# DRV8711.net
KiCad netlist of a schematic drawn in EAGLE
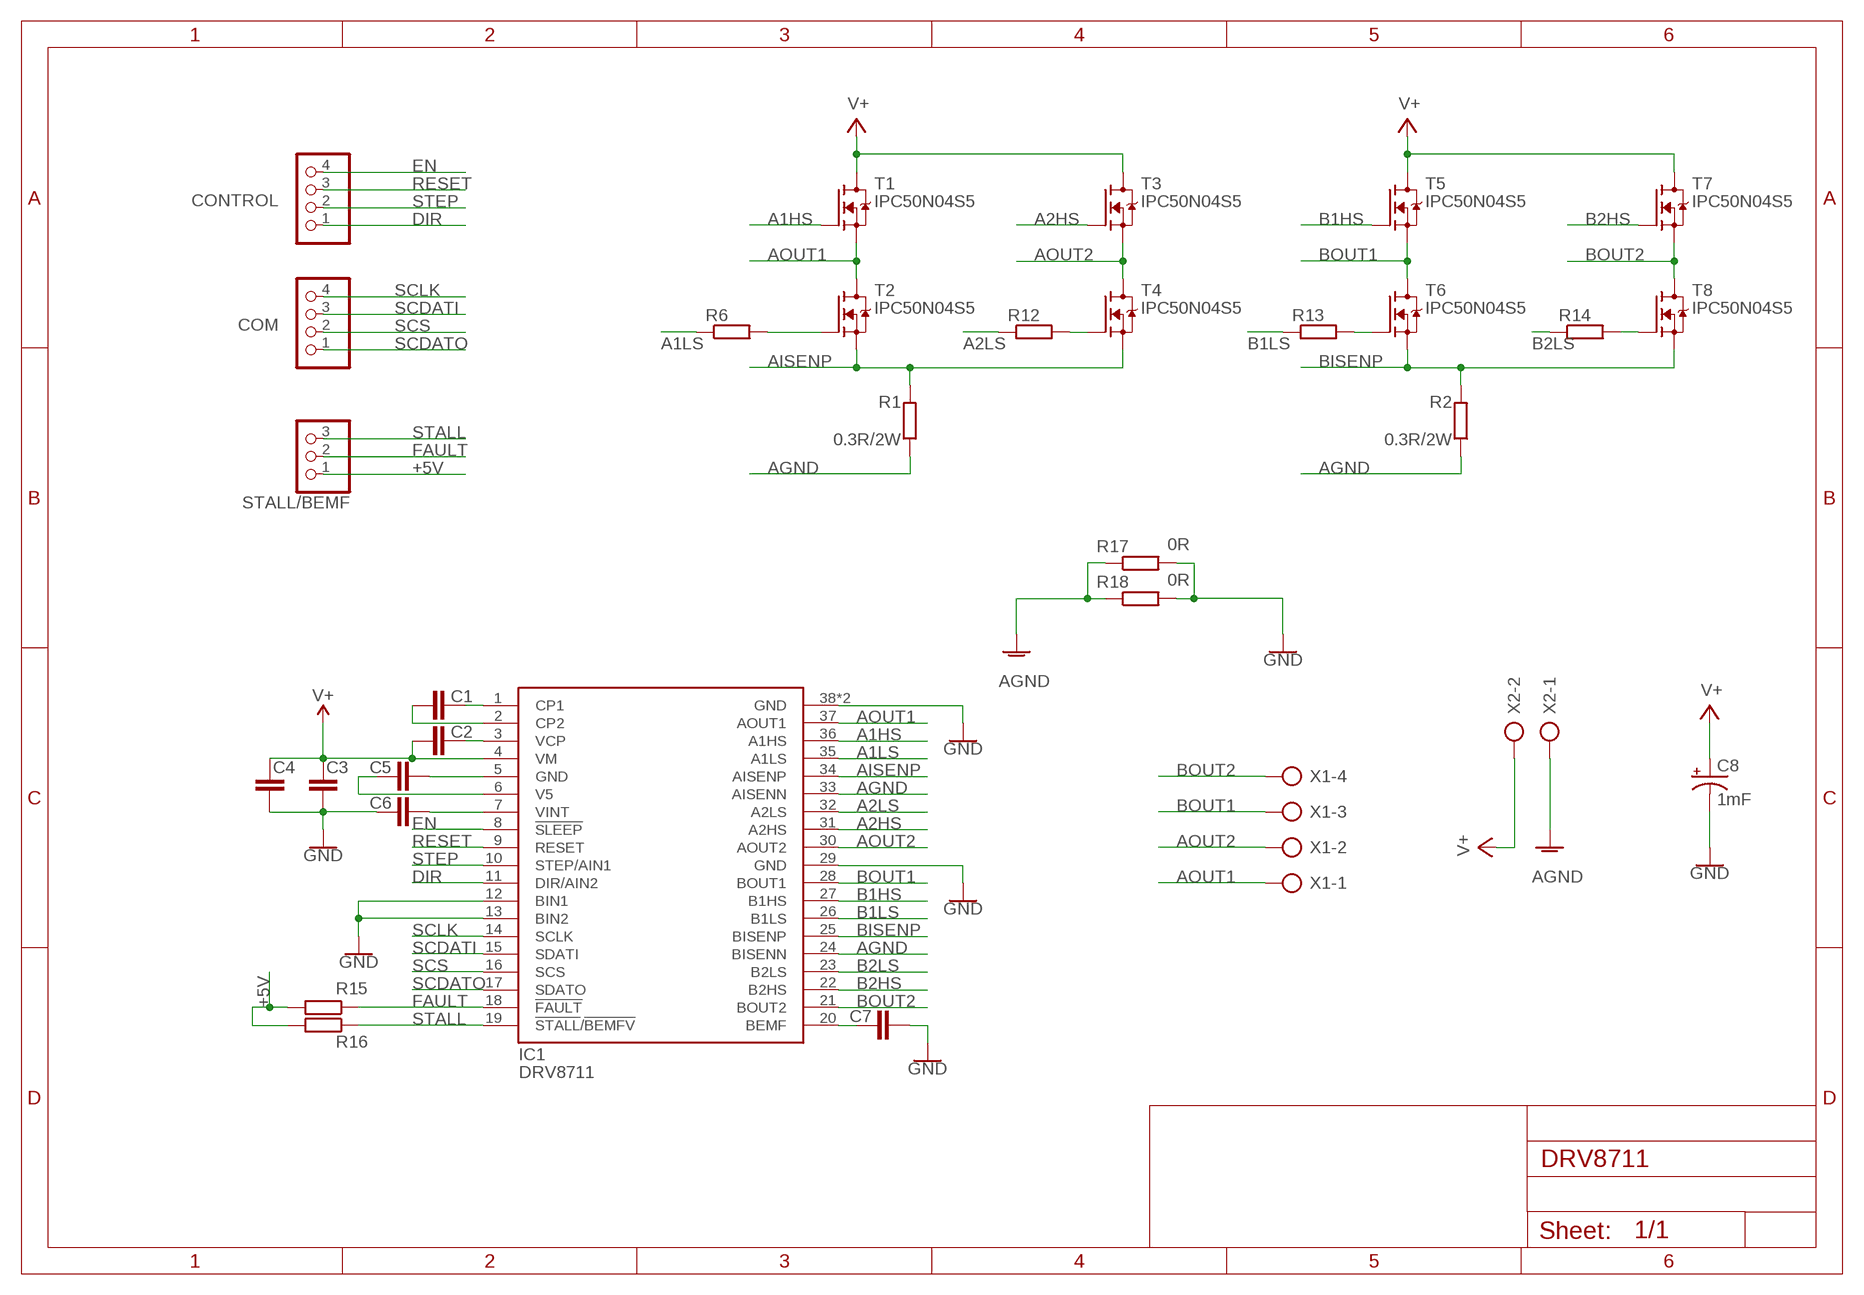
[diagram p0: schematic, sheet 1]

(export (version "E")
  (design (tool "Eeschema 10.0.6"))
  (components
    (comp (ref "C1")
      (value "C-EUC0805")
      (footprint "eagle-import:C0805")
      (libsource (lib "eagle-import") (part "C-EUC0805"))
    )
    (comp (ref "C2")
      (value "C-EUC0805")
      (footprint "eagle-import:C0805")
      (libsource (lib "eagle-import") (part "C-EUC0805"))
    )
    (comp (ref "C3")
      (value "C-EUC0805")
      (footprint "eagle-import:C0805")
      (libsource (lib "eagle-import") (part "C-EUC0805"))
    )
    (comp (ref "C4")
      (value "C-EUC0805")
      (footprint "eagle-import:C0805")
      (libsource (lib "eagle-import") (part "C-EUC0805"))
    )
    (comp (ref "C5")
      (value "C-EUC0805")
      (footprint "eagle-import:C0805")
      (libsource (lib "eagle-import") (part "C-EUC0805"))
    )
    (comp (ref "C6")
      (value "C-EUC0805")
      (footprint "eagle-import:C0805")
      (libsource (lib "eagle-import") (part "C-EUC0805"))
    )
    (comp (ref "C7")
      (value "C-EUC0805")
      (footprint "eagle-import:C0805")
      (libsource (lib "eagle-import") (part "C-EUC0805"))
    )
    (comp (ref "C8")
      (value "1mF")
      (footprint "eagle-import:CPOL-RADIAL-5MM-10MM")
      (libsource (lib "eagle-import") (part "1000UF-RADIAL-5MM-25V-20%"))
    )
    (comp (ref "COM")
      (value "PINHD-1X4")
      (footprint "eagle-import:1X04")
      (libsource (lib "eagle-import") (part "PINHD-1X4"))
    )
    (comp (ref "CONTROL")
      (value "PINHD-1X4")
      (footprint "eagle-import:1X04")
      (libsource (lib "eagle-import") (part "PINHD-1X4"))
    )
    (comp (ref "IC1")
      (value "DRV8711")
      (footprint "eagle-import:R-PDSO-G38")
      (libsource (lib "eagle-import") (part "DRV8711"))
    )
    (comp (ref "R1")
      (value "0.3R/2W")
      (footprint "eagle-import:R2512")
      (libsource (lib "eagle-import") (part "R-EU_R2512"))
    )
    (comp (ref "R2")
      (value "0.3R/2W")
      (footprint "eagle-import:R2512")
      (libsource (lib "eagle-import") (part "R-EU_R2512"))
    )
    (comp (ref "R6")
      (value "R-EU_R0805")
      (footprint "eagle-import:R0805")
      (libsource (lib "eagle-import") (part "R-EU_R0805"))
    )
    (comp (ref "R12")
      (value "R-EU_R0805")
      (footprint "eagle-import:R0805")
      (libsource (lib "eagle-import") (part "R-EU_R0805"))
    )
    (comp (ref "R13")
      (value "R-EU_R0805")
      (footprint "eagle-import:R0805")
      (libsource (lib "eagle-import") (part "R-EU_R0805"))
    )
    (comp (ref "R14")
      (value "R-EU_R0805")
      (footprint "eagle-import:R0805")
      (libsource (lib "eagle-import") (part "R-EU_R0805"))
    )
    (comp (ref "R15")
      (value "R-EU_R0805")
      (footprint "eagle-import:R0805")
      (libsource (lib "eagle-import") (part "R-EU_R0805"))
    )
    (comp (ref "R16")
      (value "R-EU_R0805")
      (footprint "eagle-import:R0805")
      (libsource (lib "eagle-import") (part "R-EU_R0805"))
    )
    (comp (ref "R17")
      (value "0R")
      (footprint "eagle-import:R0805")
      (libsource (lib "eagle-import") (part "R-EU_R0805"))
    )
    (comp (ref "R18")
      (value "0R")
      (footprint "eagle-import:R0805")
      (libsource (lib "eagle-import") (part "R-EU_R0805"))
    )
    (comp (ref "STALL/BEMF")
      (value "PINHD-1X3")
      (footprint "eagle-import:1X03")
      (libsource (lib "eagle-import") (part "PINHD-1X3"))
    )
    (comp (ref "T1")
      (value "IPC50N04S5")
      (footprint "eagle-import:PG-TDSON-8-33")
      (libsource (lib "eagle-import") (part "IPC50N04S5"))
    )
    (comp (ref "T2")
      (value "IPC50N04S5")
      (footprint "eagle-import:PG-TDSON-8-33")
      (libsource (lib "eagle-import") (part "IPC50N04S5"))
    )
    (comp (ref "T3")
      (value "IPC50N04S5")
      (footprint "eagle-import:PG-TDSON-8-33")
      (libsource (lib "eagle-import") (part "IPC50N04S5"))
    )
    (comp (ref "T4")
      (value "IPC50N04S5")
      (footprint "eagle-import:PG-TDSON-8-33")
      (libsource (lib "eagle-import") (part "IPC50N04S5"))
    )
    (comp (ref "T5")
      (value "IPC50N04S5")
      (footprint "eagle-import:PG-TDSON-8-33")
      (libsource (lib "eagle-import") (part "IPC50N04S5"))
    )
    (comp (ref "T6")
      (value "IPC50N04S5")
      (footprint "eagle-import:PG-TDSON-8-33")
      (libsource (lib "eagle-import") (part "IPC50N04S5"))
    )
    (comp (ref "T7")
      (value "IPC50N04S5")
      (footprint "eagle-import:PG-TDSON-8-33")
      (libsource (lib "eagle-import") (part "IPC50N04S5"))
    )
    (comp (ref "T8")
      (value "IPC50N04S5")
      (footprint "eagle-import:PG-TDSON-8-33")
      (libsource (lib "eagle-import") (part "IPC50N04S5"))
    )
    (comp (ref "X1")
      (value "AK500/4")
      (footprint "eagle-import:AK500_4")
      (libsource (lib "eagle-import") (part "AK500/4"))
    )
    (comp (ref "X2")
      (value "AK500/2")
      (footprint "eagle-import:AK500_2")
      (libsource (lib "eagle-import") (part "AK500/2"))
    )
  )
  (nets
    (net (code "1") (name "/+5V") (class "Default")
      (node (ref "R15") (pin "2") (pinfunction "2_2") (pintype "passive"))
      (node (ref "R16") (pin "2") (pinfunction "2_2") (pintype "passive"))
      (node (ref "STALL/BEMF") (pin "1") (pinfunction "1_1") (pintype "passive"))
    )
    (net (code "2") (name "/A1HS") (class "Default")
      (node (ref "IC1") (pin "36") (pinfunction "A1HS_36") (pintype "bidirectional"))
      (node (ref "T1") (pin "3") (pinfunction "G_3") (pintype "passive"))
    )
    (net (code "3") (name "/A1LS") (class "Default")
      (node (ref "IC1") (pin "35") (pinfunction "A1LS_35") (pintype "bidirectional"))
      (node (ref "R6") (pin "1") (pinfunction "1_1") (pintype "passive"))
    )
    (net (code "4") (name "/A2HS") (class "Default")
      (node (ref "IC1") (pin "31") (pinfunction "A2HS_31") (pintype "bidirectional"))
      (node (ref "T3") (pin "3") (pinfunction "G_3") (pintype "passive"))
    )
    (net (code "5") (name "/A2LS") (class "Default")
      (node (ref "IC1") (pin "32") (pinfunction "A2LS_32") (pintype "bidirectional"))
      (node (ref "R12") (pin "1") (pinfunction "1_1") (pintype "passive"))
    )
    (net (code "6") (name "/AISENP") (class "Default")
      (node (ref "IC1") (pin "34") (pinfunction "AISENP_34") (pintype "bidirectional"))
      (node (ref "R1") (pin "2") (pinfunction "2_2") (pintype "passive"))
      (node (ref "T2") (pin "2") (pinfunction "S_2") (pintype "passive"))
      (node (ref "T4") (pin "2") (pinfunction "S_2") (pintype "passive"))
    )
    (net (code "7") (name "/AOUT1") (class "Default")
      (node (ref "IC1") (pin "37") (pinfunction "AOUT1_37") (pintype "bidirectional"))
      (node (ref "T1") (pin "2") (pinfunction "S_2") (pintype "passive"))
      (node (ref "T2") (pin "1") (pinfunction "D_1") (pintype "passive"))
      (node (ref "X1") (pin "1") (pinfunction "KL_1") (pintype "passive"))
    )
    (net (code "8") (name "/AOUT2") (class "Default")
      (node (ref "IC1") (pin "30") (pinfunction "AOUT2_30") (pintype "bidirectional"))
      (node (ref "T3") (pin "2") (pinfunction "S_2") (pintype "passive"))
      (node (ref "T4") (pin "1") (pinfunction "D_1") (pintype "passive"))
      (node (ref "X1") (pin "2") (pinfunction "KL_2") (pintype "passive"))
    )
    (net (code "9") (name "/B1HS") (class "Default")
      (node (ref "IC1") (pin "27") (pinfunction "B1HS_27") (pintype "bidirectional"))
      (node (ref "T5") (pin "3") (pinfunction "G_3") (pintype "passive"))
    )
    (net (code "10") (name "/B1LS") (class "Default")
      (node (ref "IC1") (pin "26") (pinfunction "B1LS_26") (pintype "bidirectional"))
      (node (ref "R13") (pin "1") (pinfunction "1_1") (pintype "passive"))
    )
    (net (code "11") (name "/B2HS") (class "Default")
      (node (ref "IC1") (pin "22") (pinfunction "B2HS_22") (pintype "bidirectional"))
      (node (ref "T7") (pin "3") (pinfunction "G_3") (pintype "passive"))
    )
    (net (code "12") (name "/B2LS") (class "Default")
      (node (ref "IC1") (pin "23") (pinfunction "B2LS_23") (pintype "bidirectional"))
      (node (ref "R14") (pin "1") (pinfunction "1_1") (pintype "passive"))
    )
    (net (code "13") (name "/BISENP") (class "Default")
      (node (ref "IC1") (pin "25") (pinfunction "BISENP_25") (pintype "bidirectional"))
      (node (ref "R2") (pin "2") (pinfunction "2_2") (pintype "passive"))
      (node (ref "T6") (pin "2") (pinfunction "S_2") (pintype "passive"))
      (node (ref "T8") (pin "2") (pinfunction "S_2") (pintype "passive"))
    )
    (net (code "14") (name "/BOUT1") (class "Default")
      (node (ref "IC1") (pin "28") (pinfunction "BOUT1_28") (pintype "bidirectional"))
      (node (ref "T5") (pin "2") (pinfunction "S_2") (pintype "passive"))
      (node (ref "T6") (pin "1") (pinfunction "D_1") (pintype "passive"))
      (node (ref "X1") (pin "3") (pinfunction "KL_3") (pintype "passive"))
    )
    (net (code "15") (name "/BOUT2") (class "Default")
      (node (ref "IC1") (pin "21") (pinfunction "BOUT2_21") (pintype "bidirectional"))
      (node (ref "T7") (pin "2") (pinfunction "S_2") (pintype "passive"))
      (node (ref "T8") (pin "1") (pinfunction "D_1") (pintype "passive"))
      (node (ref "X1") (pin "4") (pinfunction "KL_4") (pintype "passive"))
    )
    (net (code "16") (name "/DIR") (class "Default")
      (node (ref "CONTROL") (pin "1") (pinfunction "1_1") (pintype "passive"))
      (node (ref "IC1") (pin "11") (pinfunction "DIR/AIN2_11") (pintype "bidirectional"))
    )
    (net (code "17") (name "/EN") (class "Default")
      (node (ref "CONTROL") (pin "4") (pinfunction "4_4") (pintype "passive"))
      (node (ref "IC1") (pin "8") (pinfunction "~{SLEEP}_8") (pintype "bidirectional"))
    )
    (net (code "18") (name "/FAULT") (class "Default")
      (node (ref "IC1") (pin "18") (pinfunction "~{FAULT}_18") (pintype "bidirectional"))
      (node (ref "R15") (pin "1") (pinfunction "1_1") (pintype "passive"))
      (node (ref "STALL/BEMF") (pin "2") (pinfunction "2_2") (pintype "passive"))
    )
    (net (code "19") (name "/RESET") (class "Default")
      (node (ref "CONTROL") (pin "3") (pinfunction "3_3") (pintype "passive"))
      (node (ref "IC1") (pin "9") (pinfunction "RESET_9") (pintype "bidirectional"))
    )
    (net (code "20") (name "/SCDATI") (class "Default")
      (node (ref "COM") (pin "3") (pinfunction "3_3") (pintype "passive"))
      (node (ref "IC1") (pin "15") (pinfunction "SDATI_15") (pintype "bidirectional"))
    )
    (net (code "21") (name "/SCDATO") (class "Default")
      (node (ref "COM") (pin "1") (pinfunction "1_1") (pintype "passive"))
      (node (ref "IC1") (pin "17") (pinfunction "SDATO_17") (pintype "bidirectional"))
    )
    (net (code "22") (name "/SCLK") (class "Default")
      (node (ref "COM") (pin "4") (pinfunction "4_4") (pintype "passive"))
      (node (ref "IC1") (pin "14") (pinfunction "SCLK_14") (pintype "bidirectional"))
    )
    (net (code "23") (name "/SCS") (class "Default")
      (node (ref "COM") (pin "2") (pinfunction "2_2") (pintype "passive"))
      (node (ref "IC1") (pin "16") (pinfunction "SCS_16") (pintype "bidirectional"))
    )
    (net (code "24") (name "/STALL") (class "Default")
      (node (ref "IC1") (pin "19") (pinfunction "~{STALL}/~{BEMFV}_19") (pintype "bidirectional"))
      (node (ref "R16") (pin "1") (pinfunction "1_1") (pintype "passive"))
      (node (ref "STALL/BEMF") (pin "3") (pinfunction "3_3") (pintype "passive"))
    )
    (net (code "25") (name "/STEP") (class "Default")
      (node (ref "CONTROL") (pin "2") (pinfunction "2_2") (pintype "passive"))
      (node (ref "IC1") (pin "10") (pinfunction "STEP/AIN1_10") (pintype "bidirectional"))
    )
    (net (code "26") (name "AGND") (class "Default")
      (node (ref "IC1") (pin "24") (pinfunction "BISENN_24") (pintype "bidirectional"))
      (node (ref "IC1") (pin "33") (pinfunction "AISENN_33") (pintype "bidirectional"))
      (node (ref "R1") (pin "1") (pinfunction "1_1") (pintype "passive"))
      (node (ref "R17") (pin "1") (pinfunction "1_1") (pintype "passive"))
      (node (ref "R18") (pin "1") (pinfunction "1_1") (pintype "passive"))
      (node (ref "R2") (pin "1") (pinfunction "1_1") (pintype "passive"))
      (node (ref "X2") (pin "1") (pinfunction "KL_1") (pintype "passive"))
    )
    (net (code "27") (name "GND") (class "Default")
      (node (ref "C3") (pin "1") (pinfunction "1_1") (pintype "passive"))
      (node (ref "C4") (pin "1") (pinfunction "1_1") (pintype "passive"))
      (node (ref "C5") (pin "1") (pinfunction "1_1") (pintype "passive"))
      (node (ref "C6") (pin "2") (pinfunction "2_2") (pintype "passive"))
      (node (ref "C7") (pin "1") (pinfunction "1_1") (pintype "passive"))
      (node (ref "C8") (pin "-") (pinfunction "-_-") (pintype "passive"))
      (node (ref "IC1") (pin "12") (pinfunction "BIN1_12") (pintype "bidirectional"))
      (node (ref "IC1") (pin "13") (pinfunction "BIN2_13") (pintype "bidirectional"))
      (node (ref "IC1") (pin "29") (pinfunction "GND_29") (pintype "bidirectional"))
      (node (ref "IC1") (pin "38") (pinfunction "GND_38") (pintype "bidirectional"))
      (node (ref "IC1") (pin "5") (pinfunction "GND_5") (pintype "bidirectional"))
      (node (ref "IC1") (pin "PAD") (pinfunction "GND_PAD") (pintype "bidirectional"))
      (node (ref "R17") (pin "2") (pinfunction "2_2") (pintype "passive"))
      (node (ref "R18") (pin "2") (pinfunction "2_2") (pintype "passive"))
    )
    (net (code "28") (name "Net-(IC1-BEMF)") (class "Default")
      (node (ref "C7") (pin "2") (pinfunction "2_2") (pintype "passive"))
      (node (ref "IC1") (pin "20") (pinfunction "BEMF_20") (pintype "bidirectional"))
    )
    (net (code "29") (name "Net-(IC1-CP1)") (class "Default")
      (node (ref "C1") (pin "2") (pinfunction "2_2") (pintype "passive"))
      (node (ref "IC1") (pin "1") (pinfunction "CP1_1") (pintype "bidirectional"))
    )
    (net (code "30") (name "Net-(IC1-CP2)") (class "Default")
      (node (ref "C1") (pin "1") (pinfunction "1_1") (pintype "passive"))
      (node (ref "IC1") (pin "2") (pinfunction "CP2_2") (pintype "bidirectional"))
    )
    (net (code "31") (name "Net-(IC1-V5)") (class "Default")
      (node (ref "C5") (pin "2") (pinfunction "2_2") (pintype "passive"))
      (node (ref "IC1") (pin "6") (pinfunction "V5_6") (pintype "bidirectional"))
    )
    (net (code "32") (name "Net-(IC1-VCP)") (class "Default")
      (node (ref "C2") (pin "2") (pinfunction "2_2") (pintype "passive"))
      (node (ref "IC1") (pin "3") (pinfunction "VCP_3") (pintype "bidirectional"))
    )
    (net (code "33") (name "Net-(IC1-VINT)") (class "Default")
      (node (ref "C6") (pin "1") (pinfunction "1_1") (pintype "passive"))
      (node (ref "IC1") (pin "7") (pinfunction "VINT_7") (pintype "bidirectional"))
    )
    (net (code "34") (name "Net-(T2-G)") (class "Default")
      (node (ref "R6") (pin "2") (pinfunction "2_2") (pintype "passive"))
      (node (ref "T2") (pin "3") (pinfunction "G_3") (pintype "passive"))
    )
    (net (code "35") (name "Net-(T4-G)") (class "Default")
      (node (ref "R12") (pin "2") (pinfunction "2_2") (pintype "passive"))
      (node (ref "T4") (pin "3") (pinfunction "G_3") (pintype "passive"))
    )
    (net (code "36") (name "Net-(T6-G)") (class "Default")
      (node (ref "R13") (pin "2") (pinfunction "2_2") (pintype "passive"))
      (node (ref "T6") (pin "3") (pinfunction "G_3") (pintype "passive"))
    )
    (net (code "37") (name "Net-(T8-G)") (class "Default")
      (node (ref "R14") (pin "2") (pinfunction "2_2") (pintype "passive"))
      (node (ref "T8") (pin "3") (pinfunction "G_3") (pintype "passive"))
    )
    (net (code "38") (name "V+") (class "Default")
      (node (ref "C2") (pin "1") (pinfunction "1_1") (pintype "passive"))
      (node (ref "C3") (pin "2") (pinfunction "2_2") (pintype "passive"))
      (node (ref "C4") (pin "2") (pinfunction "2_2") (pintype "passive"))
      (node (ref "C8") (pin "+") (pinfunction "+_+") (pintype "passive"))
      (node (ref "IC1") (pin "4") (pinfunction "VM_4") (pintype "bidirectional"))
      (node (ref "T1") (pin "1") (pinfunction "D_1") (pintype "passive"))
      (node (ref "T3") (pin "1") (pinfunction "D_1") (pintype "passive"))
      (node (ref "T5") (pin "1") (pinfunction "D_1") (pintype "passive"))
      (node (ref "T7") (pin "1") (pinfunction "D_1") (pintype "passive"))
      (node (ref "X2") (pin "2") (pinfunction "KL_2") (pintype "passive"))
    )
  )
)
